# Schematic.net
KiCad netlist of a schematic drawn in Altium Designer
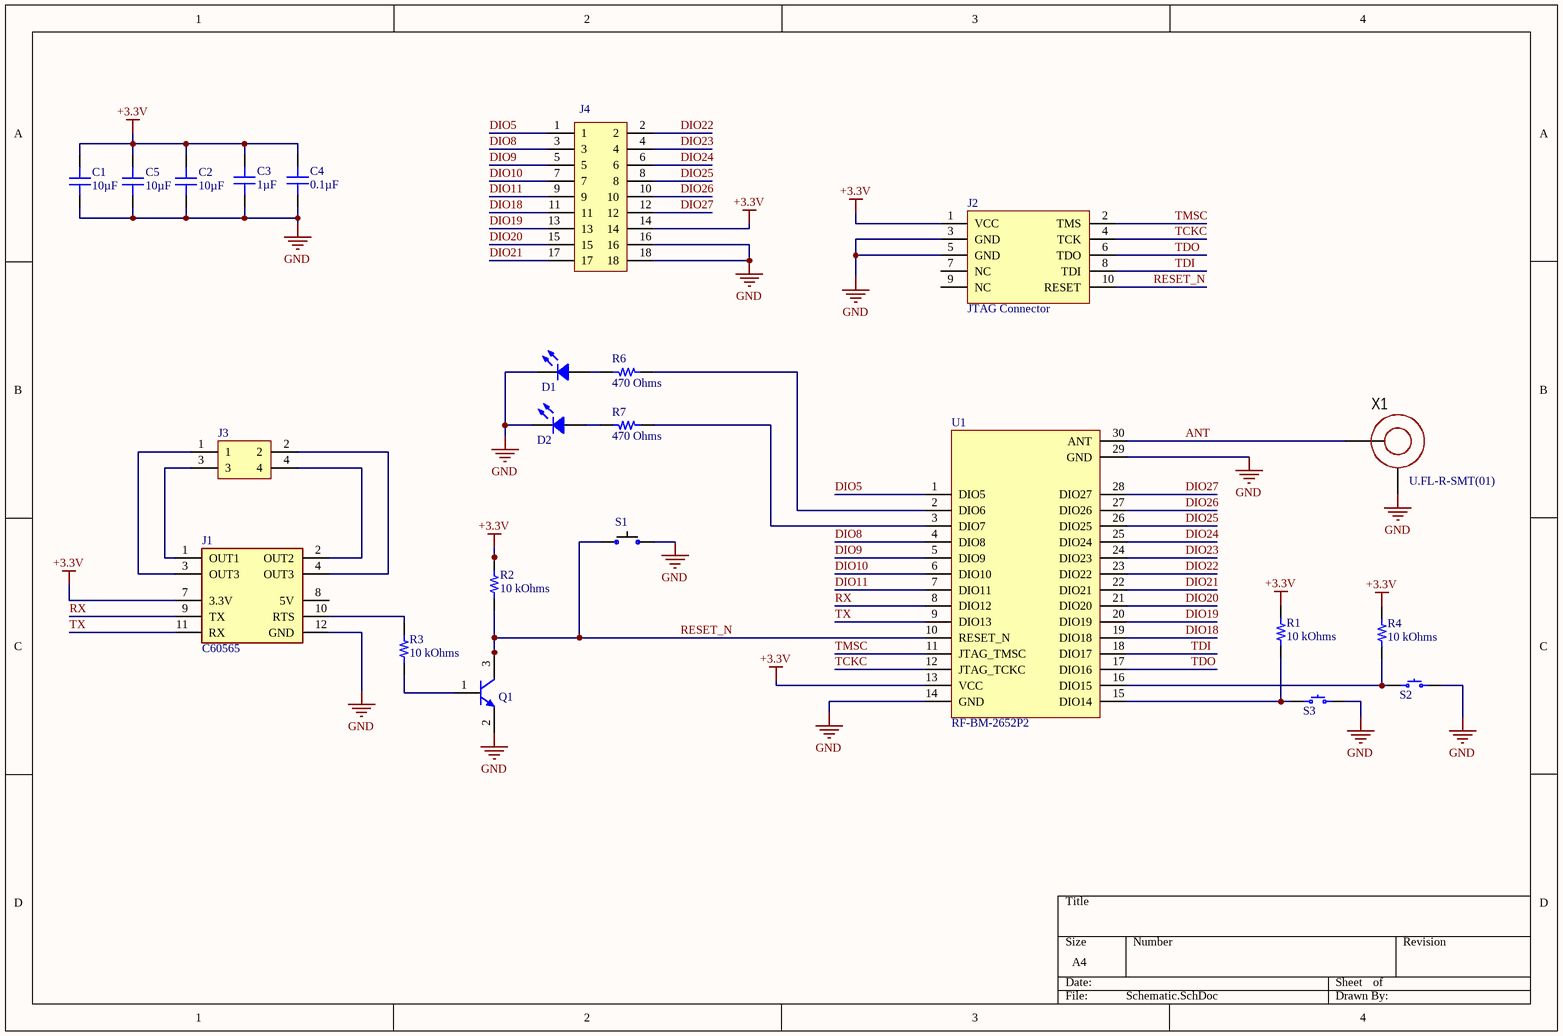
[diagram p0: Schematic.SchDoc]

(export (version "E")
  (design (tool "Eeschema 10.0.6"))
  (components
    (comp (ref "C1")
      (value "10µF")
      (footprint "CAP 0603_1608")
      (description "CAP CER 10UF 6.3V X5R 0603")
      (fields
        (field (name "MANUFACTURER") "Murata Electronics")
        (field (name "PART NUMBER") "GRM188R60J106ME47D")
      )
      (libsource (lib "Celestial") (part "Capacitor"))
    )
    (comp (ref "C2")
      (value "10µF")
      (footprint "CAP 0603_1608")
      (description "CAP CER 10UF 6.3V X5R 0603")
      (fields
        (field (name "MANUFACTURER") "Murata Electronics")
        (field (name "PART NUMBER") "GRM188R60J106ME47D")
      )
      (libsource (lib "Celestial") (part "Capacitor"))
    )
    (comp (ref "C3")
      (value "1µF")
      (footprint "CAP 0603_1608")
      (description "CAP CER 1UF 16V X7R 0603")
      (fields
        (field (name "MANUFACTURER") "Murata Electronics")
        (field (name "PART NUMBER") "GCM188R71C105KA64D")
      )
      (libsource (lib "Celestial") (part "Capacitor"))
    )
    (comp (ref "C4")
      (value "0.1µF")
      (footprint "CAP 0603_1608")
      (description "CAP CER 0.1UF 16V X7R 0603")
      (fields
        (field (name "MANUFACTURER") "Murata Electronics")
        (field (name "PART NUMBER") "GCJ188R71C104KA01D")
      )
      (libsource (lib "Celestial") (part "Capacitor"))
    )
    (comp (ref "C5")
      (value "10µF")
      (footprint "CAP 0603_1608")
      (description "CAP CER 10UF 6.3V X5R 0603")
      (fields
        (field (name "MANUFACTURER") "Murata Electronics")
        (field (name "PART NUMBER") "GRM188R60J106ME47D")
      )
      (libsource (lib "Celestial") (part "Capacitor"))
    )
    (comp (ref "D1")
      (value "Green")
      (footprint "LED 0603_1608 GREEN")
      (description "LED GREEN CLEAR CHIP SMD")
      (fields (field (name "MANUFACTURER") "Kingbright") (field (name "PART NUMBER") "APT1608CGCK"))
      (libsource (lib "Celestial") (part "LED"))
    )
    (comp (ref "D2")
      (value "Red")
      (footprint "LED 0603_1608 RED")
      (description "LED RED CLEAR CHIP SMD")
      (fields (field (name "MANUFACTURER") "Kingbright") (field (name "PART NUMBER") "APT1608EC"))
      (libsource (lib "Celestial") (part "LED"))
    )
    (comp (ref "J1")
      (value "C60565")
      (footprint "C60565")
      (description "Pin Header 12 2 right-angle，90degrees 2.54mm P=2.54mm Pin Header & Female Header RoHS")
      (fields
        (field (name "MF") "Global Connector Technology")
        (field (name "MP") "BG040-14-A-0300-0300-N-G")
      )
      (libsource (lib "WB-Connector") (part "C60565"))
    )
    (comp (ref "J2")
      (value "JTAG Connector")
      (footprint "2x1.27x10")
      (libsource (lib "Misc") (part "JTAG Connector"))
    )
    (comp (ref "J3") (value "Pins") (footprint "1.27x4") (libsource (lib "Misc") (part "Pins")))
    (comp (ref "J4") (value "GPIO") (footprint "1.27x18") (libsource (lib "Misc") (part "GPIO")))
    (comp (ref "Q1")
      (value "BC847CLT1G")
      (footprint "ON SEMI SOT-23-3")
      (description "TRANS NPN 45V 0.1A SOT23")
      (fields (field (name "MANUFACTURER") "ON Semiconductor"))
      (libsource (lib "Celestial") (part "ON SEMI NPN SOT-23-3"))
    )
    (comp (ref "R1")
      (value "10 kOhms")
      (footprint "RES 0603_1608")
      (description "RES SMD 10K OHM 0.5% 1/10W 0603")
      (fields (field (name "PART NUMBER") "RT0603DRD0710KL") (field (name "MANUFACTURER") "Yageo"))
      (libsource (lib "Celestial") (part "Resistor"))
    )
    (comp (ref "R2")
      (value "10 kOhms")
      (footprint "RES 0603_1608")
      (description "RES SMD 10K OHM 0.5% 1/10W 0603")
      (fields (field (name "PART NUMBER") "RT0603DRD0710KL") (field (name "MANUFACTURER") "Yageo"))
      (libsource (lib "Celestial") (part "Resistor"))
    )
    (comp (ref "R3")
      (value "10 kOhms")
      (footprint "RES 0603_1608")
      (description "RES SMD 10K OHM 0.5% 1/10W 0603")
      (fields (field (name "PART NUMBER") "RT0603DRD0710KL") (field (name "MANUFACTURER") "Yageo"))
      (libsource (lib "Celestial") (part "Resistor"))
    )
    (comp (ref "R4")
      (value "10 kOhms")
      (footprint "RES 0603_1608")
      (description "RES SMD 10K OHM 0.5% 1/10W 0603")
      (fields (field (name "PART NUMBER") "RT0603DRD0710KL") (field (name "MANUFACTURER") "Yageo"))
      (libsource (lib "Celestial") (part "Resistor"))
    )
    (comp (ref "R6")
      (value "470 Ohms")
      (footprint "RES 0603_1608")
      (description "RES SMD 470 OHM 1% 1/10W 0603")
      (fields (field (name "PART NUMBER") "AT0603FRE07470RL") (field (name "MANUFACTURER") "Yageo"))
      (libsource (lib "Celestial") (part "Resistor"))
    )
    (comp (ref "R7")
      (value "470 Ohms")
      (footprint "RES 0603_1608")
      (description "RES SMD 470 OHM 1% 1/10W 0603")
      (fields (field (name "PART NUMBER") "AT0603FRE07470RL") (field (name "MANUFACTURER") "Yageo"))
      (libsource (lib "Celestial") (part "Resistor"))
    )
    (comp (ref "S1") (value "K2-1107ST-A3SW-06") (footprint "Btn") (libsource (lib "Misc") (part "Btn")))
    (comp (ref "S2")
      (value "KSS331GLFS")
      (footprint "C&K KSS")
      (description "SWITCH TACTILE SPST-NO 0.05A 50V")
      (fields (field (name "MANUFACTURER") "C&K"))
      (libsource (lib "Celestial") (part "SPST-NO 2 PIN"))
    )
    (comp (ref "S3")
      (value "KSS331GLFS")
      (footprint "C&K KSS")
      (description "SWITCH TACTILE SPST-NO 0.05A 50V")
      (fields (field (name "MANUFACTURER") "C&K"))
      (libsource (lib "Celestial") (part "SPST-NO 2 PIN"))
    )
    (comp (ref "U1")
      (value "RF-BM-2652P2")
      (footprint "RF-BM-2652P2")
      (libsource (lib "RF-BM-2652P2") (part "RF-BM-2652P2"))
    )
    (comp (ref "X1")
      (value "U.FL-R-SMT(01)")
      (footprint "CON: u.Fl")
      (fields
        (field (name "MANUFACTURER") "Hirose Electric")
        (field (name "VALUEMANUFACTURERPARTNUMBER") "Connector u.FL, 50 Ohm, 6GHz")
      )
      (libsource (lib "Misc") (part "U.FL-R-SMT(01)"))
    )
  )
  (nets
    (net (code "1") (name "+3.3V") (class "Default")
      (node (ref "C1") (pin "1") (pinfunction "1_1") (pintype "passive"))
      (node (ref "C2") (pin "1") (pinfunction "1_1") (pintype "passive"))
      (node (ref "C3") (pin "1") (pinfunction "1_1") (pintype "passive"))
      (node (ref "C4") (pin "2") (pinfunction "2_2") (pintype "passive"))
      (node (ref "C5") (pin "1") (pinfunction "1_1") (pintype "passive"))
      (node (ref "J1") (pin "7") (pinfunction "3.3V_7") (pintype "passive"))
      (node (ref "J2") (pin "1") (pinfunction "VCC_1") (pintype "passive"))
      (node (ref "J4") (pin "14") (pinfunction "14_14") (pintype "passive"))
      (node (ref "R1") (pin "1") (pinfunction "1_1") (pintype "passive"))
      (node (ref "R2") (pin "1") (pinfunction "1_1") (pintype "passive"))
      (node (ref "R4") (pin "1") (pinfunction "1_1") (pintype "passive"))
      (node (ref "U1") (pin "13") (pinfunction "VCC_13") (pintype "passive"))
    )
    (net (code "2") (name "/ANT") (class "Default")
      (node (ref "U1") (pin "30") (pinfunction "ANT_30") (pintype "passive"))
      (node (ref "X1") (pin "1") (pinfunction "1_1") (pintype "passive"))
    )
    (net (code "3") (name "/DIO5") (class "Default")
      (node (ref "J4") (pin "1") (pinfunction "1_1") (pintype "passive"))
      (node (ref "U1") (pin "1") (pinfunction "DIO5_1") (pintype "passive"))
    )
    (net (code "4") (name "/DIO8") (class "Default")
      (node (ref "J4") (pin "3") (pinfunction "3_3") (pintype "passive"))
      (node (ref "U1") (pin "4") (pinfunction "DIO8_4") (pintype "passive"))
    )
    (net (code "5") (name "/DIO9") (class "Default")
      (node (ref "J4") (pin "5") (pinfunction "5_5") (pintype "passive"))
      (node (ref "U1") (pin "5") (pinfunction "DIO9_5") (pintype "passive"))
    )
    (net (code "6") (name "/DIO10") (class "Default")
      (node (ref "J4") (pin "7") (pinfunction "7_7") (pintype "passive"))
      (node (ref "U1") (pin "6") (pinfunction "DIO10_6") (pintype "passive"))
    )
    (net (code "7") (name "/DIO11") (class "Default")
      (node (ref "J4") (pin "9") (pinfunction "9_9") (pintype "passive"))
      (node (ref "U1") (pin "7") (pinfunction "DIO11_7") (pintype "passive"))
    )
    (net (code "8") (name "/DIO18") (class "Default")
      (node (ref "J4") (pin "11") (pinfunction "11_11") (pintype "passive"))
      (node (ref "U1") (pin "19") (pinfunction "DIO18_19") (pintype "passive"))
    )
    (net (code "9") (name "/DIO19") (class "Default")
      (node (ref "J4") (pin "13") (pinfunction "13_13") (pintype "passive"))
      (node (ref "U1") (pin "20") (pinfunction "DIO19_20") (pintype "passive"))
    )
    (net (code "10") (name "/DIO20") (class "Default")
      (node (ref "J4") (pin "15") (pinfunction "15_15") (pintype "passive"))
      (node (ref "U1") (pin "21") (pinfunction "DIO20_21") (pintype "passive"))
    )
    (net (code "11") (name "/DIO21") (class "Default")
      (node (ref "J4") (pin "17") (pinfunction "17_17") (pintype "passive"))
      (node (ref "U1") (pin "22") (pinfunction "DIO21_22") (pintype "passive"))
    )
    (net (code "12") (name "/DIO22") (class "Default")
      (node (ref "J4") (pin "2") (pinfunction "2_2") (pintype "passive"))
      (node (ref "U1") (pin "23") (pinfunction "DIO22_23") (pintype "passive"))
    )
    (net (code "13") (name "/DIO23") (class "Default")
      (node (ref "J4") (pin "4") (pinfunction "4_4") (pintype "passive"))
      (node (ref "U1") (pin "24") (pinfunction "DIO23_24") (pintype "passive"))
    )
    (net (code "14") (name "/DIO24") (class "Default")
      (node (ref "J4") (pin "6") (pinfunction "6_6") (pintype "passive"))
      (node (ref "U1") (pin "25") (pinfunction "DIO24_25") (pintype "passive"))
    )
    (net (code "15") (name "/DIO25") (class "Default")
      (node (ref "J4") (pin "8") (pinfunction "8_8") (pintype "passive"))
      (node (ref "U1") (pin "26") (pinfunction "DIO25_26") (pintype "passive"))
    )
    (net (code "16") (name "/DIO26") (class "Default")
      (node (ref "J4") (pin "10") (pinfunction "10_10") (pintype "passive"))
      (node (ref "U1") (pin "27") (pinfunction "DIO26_27") (pintype "passive"))
    )
    (net (code "17") (name "/DIO27") (class "Default")
      (node (ref "J4") (pin "12") (pinfunction "12_12") (pintype "passive"))
      (node (ref "U1") (pin "28") (pinfunction "DIO27_28") (pintype "passive"))
    )
    (net (code "18") (name "/RESET_N") (class "Default")
      (node (ref "J2") (pin "10") (pinfunction "RESET_10") (pintype "passive"))
      (node (ref "Q1") (pin "3") (pinfunction "C_3") (pintype "passive"))
      (node (ref "R2") (pin "2") (pinfunction "2_2") (pintype "passive"))
      (node (ref "S1") (pin "1") (pinfunction "1_1") (pintype "passive"))
      (node (ref "U1") (pin "10") (pinfunction "RESET_N_10") (pintype "passive"))
    )
    (net (code "19") (name "/RX") (class "Default")
      (node (ref "J1") (pin "9") (pinfunction "TX_9") (pintype "passive"))
      (node (ref "U1") (pin "8") (pinfunction "DIO12_8") (pintype "passive"))
    )
    (net (code "20") (name "/TCKC") (class "Default")
      (node (ref "J2") (pin "4") (pinfunction "TCK_4") (pintype "passive"))
      (node (ref "U1") (pin "12") (pinfunction "JTAG_TCKC_12") (pintype "passive"))
    )
    (net (code "21") (name "/TDI") (class "Default")
      (node (ref "J2") (pin "8") (pinfunction "TDI_8") (pintype "passive"))
      (node (ref "U1") (pin "18") (pinfunction "DIO17_18") (pintype "passive"))
    )
    (net (code "22") (name "/TDO") (class "Default")
      (node (ref "J2") (pin "6") (pinfunction "TDO_6") (pintype "passive"))
      (node (ref "U1") (pin "17") (pinfunction "DIO16_17") (pintype "passive"))
    )
    (net (code "23") (name "/TMSC") (class "Default")
      (node (ref "J2") (pin "2") (pinfunction "TMS_2") (pintype "passive"))
      (node (ref "U1") (pin "11") (pinfunction "JTAG_TMSC_11") (pintype "passive"))
    )
    (net (code "24") (name "/TX") (class "Default")
      (node (ref "J1") (pin "11") (pinfunction "RX_11") (pintype "passive"))
      (node (ref "U1") (pin "9") (pinfunction "DIO13_9") (pintype "passive"))
    )
    (net (code "25") (name "GND") (class "Default")
      (node (ref "C1") (pin "2") (pinfunction "2_2") (pintype "passive"))
      (node (ref "C2") (pin "2") (pinfunction "2_2") (pintype "passive"))
      (node (ref "C3") (pin "2") (pinfunction "2_2") (pintype "passive"))
      (node (ref "C4") (pin "1") (pinfunction "1_1") (pintype "passive"))
      (node (ref "C5") (pin "2") (pinfunction "2_2") (pintype "passive"))
      (node (ref "D1") (pin "2") (pinfunction "2_2") (pintype "passive"))
      (node (ref "D2") (pin "2") (pinfunction "2_2") (pintype "passive"))
      (node (ref "J1") (pin "12") (pinfunction "GND_12") (pintype "passive"))
      (node (ref "J2") (pin "3") (pinfunction "GND_3") (pintype "passive"))
      (node (ref "J2") (pin "5") (pinfunction "GND_5") (pintype "passive"))
      (node (ref "J4") (pin "16") (pinfunction "16_16") (pintype "passive"))
      (node (ref "J4") (pin "18") (pinfunction "18_18") (pintype "passive"))
      (node (ref "Q1") (pin "2") (pinfunction "E_2") (pintype "passive"))
      (node (ref "S1") (pin "2") (pinfunction "2_2") (pintype "passive"))
      (node (ref "S2") (pin "2") (pinfunction "2_2") (pintype "passive"))
      (node (ref "S3") (pin "2") (pinfunction "2_2") (pintype "passive"))
      (node (ref "U1") (pin "14") (pinfunction "GND_14") (pintype "passive"))
      (node (ref "U1") (pin "29") (pinfunction "GND_29") (pintype "passive"))
      (node (ref "X1") (pin "2") (pinfunction "2_2") (pintype "passive"))
    )
    (net (code "26") (name "Net-(D1-Pad1)") (class "Default")
      (node (ref "D1") (pin "1") (pinfunction "1_1") (pintype "passive"))
      (node (ref "R6") (pin "1") (pinfunction "1_1") (pintype "passive"))
    )
    (net (code "27") (name "Net-(D2-Pad1)") (class "Default")
      (node (ref "D2") (pin "1") (pinfunction "1_1") (pintype "passive"))
      (node (ref "R7") (pin "1") (pinfunction "1_1") (pintype "passive"))
    )
    (net (code "28") (name "Net-(J1-OUT1)") (class "Default")
      (node (ref "J1") (pin "1") (pinfunction "OUT1_1") (pintype "passive"))
      (node (ref "J3") (pin "3") (pinfunction "3_3") (pintype "passive"))
    )
    (net (code "29") (name "Net-(J1-OUT2)") (class "Default")
      (node (ref "J1") (pin "2") (pinfunction "OUT2_2") (pintype "passive"))
      (node (ref "J3") (pin "4") (pinfunction "4_4") (pintype "passive"))
    )
    (net (code "30") (name "Net-(J1-OUT3-Pad3)") (class "Default")
      (node (ref "J1") (pin "3") (pinfunction "OUT3_3") (pintype "passive"))
      (node (ref "J3") (pin "1") (pinfunction "1_1") (pintype "passive"))
    )
    (net (code "31") (name "Net-(J1-OUT3-Pad4)") (class "Default")
      (node (ref "J1") (pin "4") (pinfunction "OUT3_4") (pintype "passive"))
      (node (ref "J3") (pin "2") (pinfunction "2_2") (pintype "passive"))
    )
    (net (code "32") (name "Net-(J1-RTS)") (class "Default")
      (node (ref "J1") (pin "10") (pinfunction "RTS_10") (pintype "passive"))
      (node (ref "R3") (pin "1") (pinfunction "1_1") (pintype "passive"))
    )
    (net (code "33") (name "Net-(Q1-B)") (class "Default")
      (node (ref "Q1") (pin "1") (pinfunction "B_1") (pintype "passive"))
      (node (ref "R3") (pin "2") (pinfunction "2_2") (pintype "passive"))
    )
    (net (code "34") (name "Net-(U1-DIO6)") (class "Default")
      (node (ref "R6") (pin "2") (pinfunction "2_2") (pintype "passive"))
      (node (ref "U1") (pin "2") (pinfunction "DIO6_2") (pintype "passive"))
    )
    (net (code "35") (name "Net-(U1-DIO7)") (class "Default")
      (node (ref "R7") (pin "2") (pinfunction "2_2") (pintype "passive"))
      (node (ref "U1") (pin "3") (pinfunction "DIO7_3") (pintype "passive"))
    )
    (net (code "36") (name "Net-(U1-DIO14)") (class "Default")
      (node (ref "R1") (pin "2") (pinfunction "2_2") (pintype "passive"))
      (node (ref "S3") (pin "1") (pinfunction "1_1") (pintype "passive"))
      (node (ref "U1") (pin "15") (pinfunction "DIO14_15") (pintype "passive"))
    )
    (net (code "37") (name "Net-(U1-DIO15)") (class "Default")
      (node (ref "R4") (pin "2") (pinfunction "2_2") (pintype "passive"))
      (node (ref "S2") (pin "1") (pinfunction "1_1") (pintype "passive"))
      (node (ref "U1") (pin "16") (pinfunction "DIO15_16") (pintype "passive"))
    )
    (net (code "38") (name "unconnected-(J1-5V-Pad8)") (class "Default")
      (node (ref "J1") (pin "8") (pinfunction "5V_8") (pintype "passive"))
    )
    (net (code "39") (name "unconnected-(J2-NC-Pad7)") (class "Default")
      (node (ref "J2") (pin "7") (pinfunction "NC_7") (pintype "passive"))
    )
    (net (code "40") (name "unconnected-(J2-NC-Pad9)") (class "Default")
      (node (ref "J2") (pin "9") (pinfunction "NC_9") (pintype "passive"))
    )
  )
)
